# AVR-USB2SERIAL.net
KiCad netlist of a schematic drawn in EAGLE
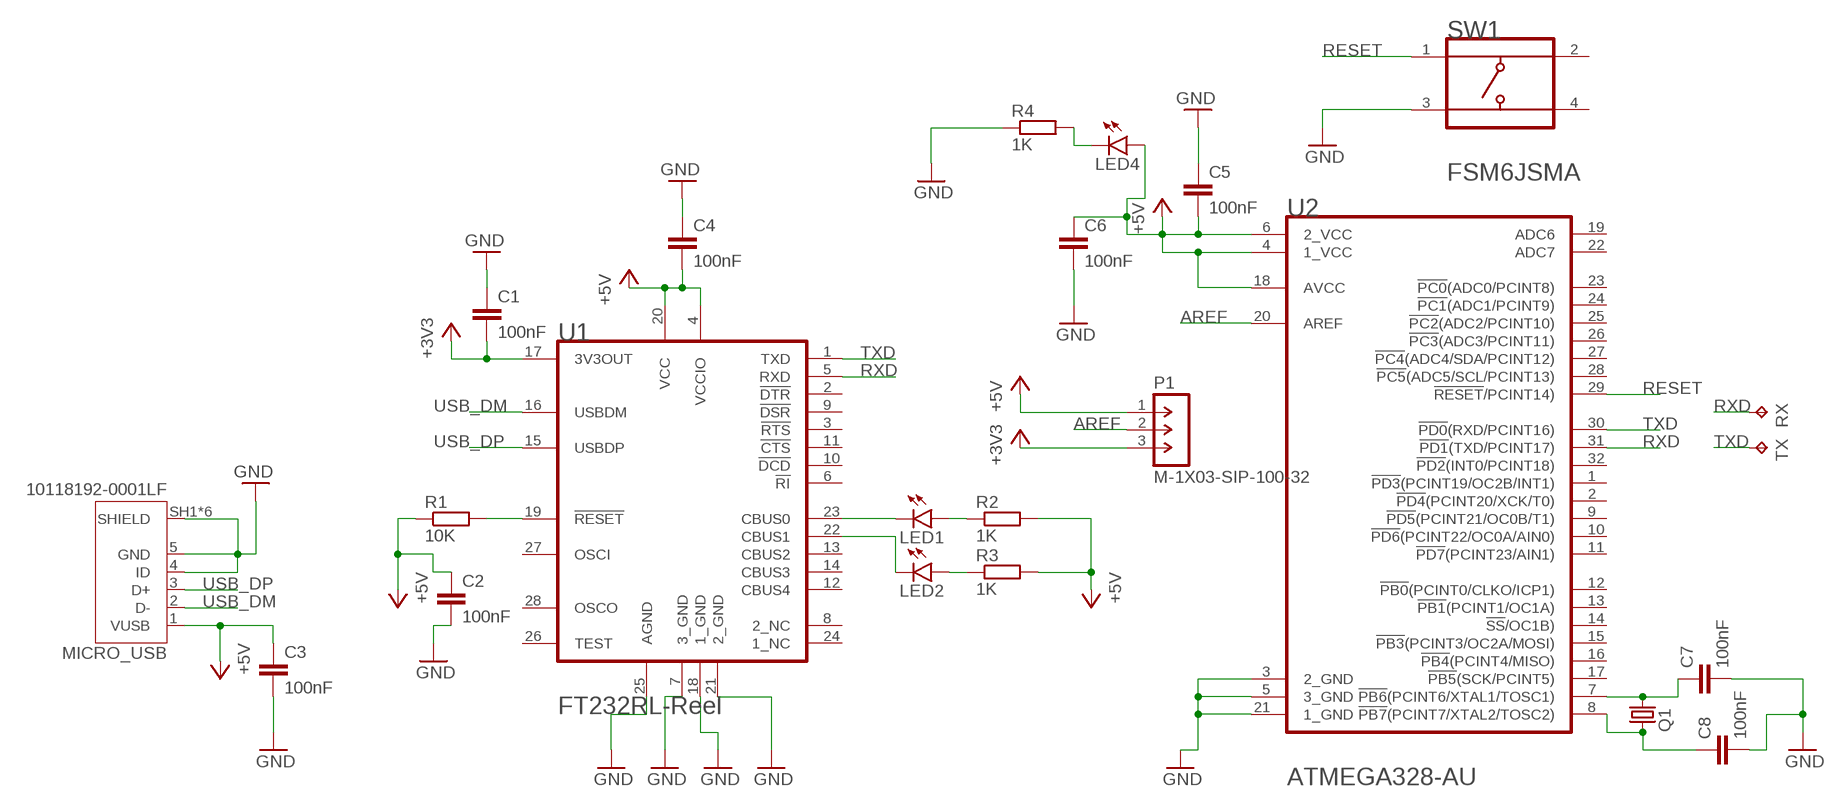
[diagram p0: schematic, sheet 1]

(export (version "E")
  (design (tool "Eeschema 10.0.6"))
  (components
    (comp (ref "C1")
      (value "100nF")
      (footprint "eagle-import:C0805")
      (libsource (lib "eagle-import") (part "C-EUC0805"))
    )
    (comp (ref "C2")
      (value "100nF")
      (footprint "eagle-import:C0805")
      (libsource (lib "eagle-import") (part "C-EUC0805"))
    )
    (comp (ref "C3")
      (value "100nF")
      (footprint "eagle-import:C0805")
      (libsource (lib "eagle-import") (part "C-EUC0805"))
    )
    (comp (ref "C4")
      (value "100nF")
      (footprint "eagle-import:C0805")
      (libsource (lib "eagle-import") (part "C-EUC0805"))
    )
    (comp (ref "C5")
      (value "100nF")
      (footprint "eagle-import:C0805")
      (libsource (lib "eagle-import") (part "C-EUC0805"))
    )
    (comp (ref "C6")
      (value "100nF")
      (footprint "eagle-import:C0805")
      (libsource (lib "eagle-import") (part "C-EUC0805"))
    )
    (comp (ref "C7")
      (value "100nF")
      (footprint "eagle-import:C0805")
      (libsource (lib "eagle-import") (part "C-EUC0805"))
    )
    (comp (ref "C8")
      (value "100nF")
      (footprint "eagle-import:C0805")
      (libsource (lib "eagle-import") (part "C-EUC0805"))
    )
    (comp (ref "LED1")
      (value "LEDCHIPLED_0805")
      (footprint "eagle-import:CHIPLED_0805")
      (libsource (lib "eagle-import") (part "LEDCHIPLED_0805"))
    )
    (comp (ref "LED2")
      (value "LEDCHIPLED_0805")
      (footprint "eagle-import:CHIPLED_0805")
      (libsource (lib "eagle-import") (part "LEDCHIPLED_0805"))
    )
    (comp (ref "LED4")
      (value "LEDCHIPLED_0805")
      (footprint "eagle-import:CHIPLED_0805")
      (libsource (lib "eagle-import") (part "LEDCHIPLED_0805"))
    )
    (comp (ref "MICRO_USB")
      (value "10118192-0001LF")
      (footprint "eagle-import:AMPHENOL_10118192-0001LF")
      (fields (field (name "MF") "Amphenol ICC"))
      (libsource (lib "eagle-import") (part "10118192-0001LF"))
    )
    (comp (ref "P1")
      (value "M-1X03-SIP-100-32")
      (footprint "eagle-import:SIP-100-03-32")
      (libsource (lib "eagle-import") (part "M-1X03-SIP-100-32"))
    )
    (comp (ref "Q1")
      (value "CRYSTALHC49UP")
      (footprint "eagle-import:HC49UP")
      (libsource (lib "eagle-import") (part "CRYSTALHC49UP"))
    )
    (comp (ref "R1")
      (value "10K")
      (footprint "eagle-import:R0805")
      (libsource (lib "eagle-import") (part "R-EU_R0805"))
    )
    (comp (ref "R2")
      (value "1K")
      (footprint "eagle-import:R0805")
      (libsource (lib "eagle-import") (part "R-EU_R0805"))
    )
    (comp (ref "R3")
      (value "1K")
      (footprint "eagle-import:R0805")
      (libsource (lib "eagle-import") (part "R-EU_R0805"))
    )
    (comp (ref "R4")
      (value "1K")
      (footprint "eagle-import:R0805")
      (libsource (lib "eagle-import") (part "R-EU_R0805"))
    )
    (comp (ref "RX")
      (value "TPB1,27")
      (footprint "eagle-import:B1,27")
      (libsource (lib "eagle-import") (part "TPB1,27"))
    )
    (comp (ref "SW1")
      (value "TE_CONNECTIVITY_ALCOSWITCH_FSM6JSMATE_CONNECTIVITY_ALCOSWITCH_FSM6JSMA_0_0")
      (footprint "eagle-import:TE_CONNECTIVITY_ALCOSWITCH_FSM6JSMA_0")
      (fields (field (name "MF") "TE Connectivity Alcoswitch") (field (name "MPN") "FSM6JSMA"))
      (libsource (lib "eagle-import") (part "TE_CONNECTIVITY_ALCOSWITCH_FSM6JSMATE_CONNECTIVITY_ALCOSWITCH_FSM6JSMA_0_0"))
    )
    (comp (ref "TX")
      (value "TPB1,27")
      (footprint "eagle-import:B1,27")
      (libsource (lib "eagle-import") (part "TPB1,27"))
    )
    (comp (ref "U1")
      (value "FTDI_FT232RL-REELFTDI_FT232RL-REEL_0_0")
      (footprint "eagle-import:FTDI_FT232RL-REEL_0")
      (fields (field (name "MF") "FTDI") (field (name "MPN") "FT232RL-Reel"))
      (libsource (lib "eagle-import") (part "FTDI_FT232RL-REELFTDI_FT232RL-REEL_0_0"))
    )
    (comp (ref "U2")
      (value "MICROCHIP_-_ATMEL_ATMEGA328-AUMICROCHIP_-_ATMEL_ATMEGA328-AU_0_0")
      (footprint "eagle-import:MICROCHIP_-_ATMEL_ATMEGA328-AU_0")
      (fields (field (name "MF") "Microchip / Atmel") (field (name "MPN") "ATMEGA328-AU"))
      (libsource (lib "eagle-import") (part "MICROCHIP_-_ATMEL_ATMEGA328-AUMICROCHIP_-_ATMEL_ATMEGA328-AU_0_0"))
    )
  )
  (nets
    (net (code "1") (name "+3V3") (class "Default")
      (node (ref "C1") (pin "2") (pinfunction "2_2") (pintype "passive"))
      (node (ref "P1") (pin "3") (pinfunction "3_3") (pintype "passive"))
      (node (ref "U1") (pin "17") (pinfunction "3V3OUT_17") (pintype "output"))
    )
    (net (code "2") (name "+5V") (class "Default")
      (node (ref "C2") (pin "1") (pinfunction "1_1") (pintype "passive"))
      (node (ref "C3") (pin "1") (pinfunction "1_1") (pintype "passive"))
      (node (ref "C4") (pin "2") (pinfunction "2_2") (pintype "passive"))
      (node (ref "C5") (pin "2") (pinfunction "2_2") (pintype "passive"))
      (node (ref "C6") (pin "1") (pinfunction "1_1") (pintype "passive"))
      (node (ref "LED4") (pin "A") (pinfunction "A_A") (pintype "passive"))
      (node (ref "MICRO_USB") (pin "1") (pinfunction "VUSB_1") (pintype "passive"))
      (node (ref "P1") (pin "1") (pinfunction "1_1") (pintype "passive"))
      (node (ref "R1") (pin "1") (pinfunction "1_1") (pintype "passive"))
      (node (ref "R2") (pin "2") (pinfunction "2_2") (pintype "passive"))
      (node (ref "R3") (pin "2") (pinfunction "2_2") (pintype "passive"))
      (node (ref "U1") (pin "20") (pinfunction "VCC_20") (pintype "power_in"))
      (node (ref "U1") (pin "4") (pinfunction "VCCIO_4") (pintype "power_in"))
      (node (ref "U2") (pin "18") (pinfunction "AVCC_18") (pintype "power_in"))
      (node (ref "U2") (pin "4") (pinfunction "1_VCC_4") (pintype "power_in"))
      (node (ref "U2") (pin "6") (pinfunction "2_VCC_6") (pintype "power_in"))
    )
    (net (code "3") (name "/AREF") (class "Default")
      (node (ref "P1") (pin "2") (pinfunction "2_2") (pintype "passive"))
      (node (ref "U2") (pin "20") (pinfunction "AREF_20") (pintype "passive"))
    )
    (net (code "4") (name "/RESET") (class "Default")
      (node (ref "SW1") (pin "1") (pinfunction "1_1") (pintype "passive"))
      (node (ref "U2") (pin "29") (pinfunction "~{RESET}/PCINT14)_29") (pintype "bidirectional"))
    )
    (net (code "5") (name "/RXD") (class "Default")
      (node (ref "RX") (pin "TP") (pinfunction "TP_TP") (pintype "input"))
      (node (ref "U1") (pin "5") (pinfunction "RXD_5") (pintype "input"))
      (node (ref "U2") (pin "31") (pinfunction "~{PD1}(TXD/PCINT17)_31") (pintype "bidirectional"))
    )
    (net (code "6") (name "/TXD") (class "Default")
      (node (ref "TX") (pin "TP") (pinfunction "TP_TP") (pintype "input"))
      (node (ref "U1") (pin "1") (pinfunction "TXD_1") (pintype "output"))
      (node (ref "U2") (pin "30") (pinfunction "~{PD0}(RXD/PCINT16)_30") (pintype "bidirectional"))
    )
    (net (code "7") (name "/USB_DM") (class "Default")
      (node (ref "MICRO_USB") (pin "2") (pinfunction "D-_2") (pintype "passive"))
      (node (ref "U1") (pin "16") (pinfunction "USBDM_16") (pintype "bidirectional"))
    )
    (net (code "8") (name "/USB_DP") (class "Default")
      (node (ref "MICRO_USB") (pin "3") (pinfunction "D+_3") (pintype "passive"))
      (node (ref "U1") (pin "15") (pinfunction "USBDP_15") (pintype "bidirectional"))
    )
    (net (code "9") (name "GND") (class "Default")
      (node (ref "C1") (pin "1") (pinfunction "1_1") (pintype "passive"))
      (node (ref "C2") (pin "2") (pinfunction "2_2") (pintype "passive"))
      (node (ref "C3") (pin "2") (pinfunction "2_2") (pintype "passive"))
      (node (ref "C4") (pin "1") (pinfunction "1_1") (pintype "passive"))
      (node (ref "C5") (pin "1") (pinfunction "1_1") (pintype "passive"))
      (node (ref "C6") (pin "2") (pinfunction "2_2") (pintype "passive"))
      (node (ref "C7") (pin "2") (pinfunction "2_2") (pintype "passive"))
      (node (ref "C8") (pin "2") (pinfunction "2_2") (pintype "passive"))
      (node (ref "MICRO_USB") (pin "4") (pinfunction "ID_4") (pintype "passive"))
      (node (ref "MICRO_USB") (pin "5") (pinfunction "GND_5") (pintype "passive"))
      (node (ref "MICRO_USB") (pin "SH1") (pinfunction "SHIELD_SH1") (pintype "passive"))
      (node (ref "MICRO_USB") (pin "SH2") (pinfunction "SHIELD_SH2") (pintype "passive"))
      (node (ref "MICRO_USB") (pin "SH3") (pinfunction "SHIELD_SH3") (pintype "passive"))
      (node (ref "MICRO_USB") (pin "SH4") (pinfunction "SHIELD_SH4") (pintype "passive"))
      (node (ref "MICRO_USB") (pin "SH5") (pinfunction "SHIELD_SH5") (pintype "passive"))
      (node (ref "MICRO_USB") (pin "SH6") (pinfunction "SHIELD_SH6") (pintype "passive"))
      (node (ref "R4") (pin "1") (pinfunction "1_1") (pintype "passive"))
      (node (ref "SW1") (pin "3") (pinfunction "3_3") (pintype "passive"))
      (node (ref "U1") (pin "18") (pinfunction "1_GND_18") (pintype "power_in"))
      (node (ref "U1") (pin "21") (pinfunction "2_GND_21") (pintype "power_in"))
      (node (ref "U1") (pin "25") (pinfunction "AGND_25") (pintype "power_in"))
      (node (ref "U1") (pin "7") (pinfunction "3_GND_7") (pintype "power_in"))
      (node (ref "U2") (pin "21") (pinfunction "1_GND_21") (pintype "power_in"))
      (node (ref "U2") (pin "3") (pinfunction "2_GND_3") (pintype "power_in"))
      (node (ref "U2") (pin "5") (pinfunction "3_GND_5") (pintype "power_in"))
    )
    (net (code "10") (name "Net-(LED1-PadA)") (class "Default")
      (node (ref "LED1") (pin "A") (pinfunction "A_A") (pintype "passive"))
      (node (ref "R2") (pin "1") (pinfunction "1_1") (pintype "passive"))
    )
    (net (code "11") (name "Net-(LED2-PadA)") (class "Default")
      (node (ref "LED2") (pin "A") (pinfunction "A_A") (pintype "passive"))
      (node (ref "R3") (pin "1") (pinfunction "1_1") (pintype "passive"))
    )
    (net (code "12") (name "Net-(LED4-PadC)") (class "Default")
      (node (ref "LED4") (pin "C") (pinfunction "C_C") (pintype "passive"))
      (node (ref "R4") (pin "2") (pinfunction "2_2") (pintype "passive"))
    )
    (net (code "13") (name "Net-(U1-CBUS0)") (class "Default")
      (node (ref "LED1") (pin "C") (pinfunction "C_C") (pintype "passive"))
      (node (ref "U1") (pin "23") (pinfunction "CBUS0_23") (pintype "bidirectional"))
    )
    (net (code "14") (name "Net-(U1-CBUS1)") (class "Default")
      (node (ref "LED2") (pin "C") (pinfunction "C_C") (pintype "passive"))
      (node (ref "U1") (pin "22") (pinfunction "CBUS1_22") (pintype "bidirectional"))
    )
    (net (code "15") (name "Net-(U1-~{RESET})") (class "Default")
      (node (ref "R1") (pin "2") (pinfunction "2_2") (pintype "passive"))
      (node (ref "U1") (pin "19") (pinfunction "~{RESET}_19") (pintype "input"))
    )
    (net (code "16") (name "Net-(U2-~{PB6}(PCINT6{slash}XTAL1{slash}TOSC1))") (class "Default")
      (node (ref "C7") (pin "1") (pinfunction "1_1") (pintype "passive"))
      (node (ref "Q1") (pin "2") (pinfunction "2_2") (pintype "passive"))
      (node (ref "U2") (pin "7") (pinfunction "~{PB6}(PCINT6/XTAL1/TOSC1)_7") (pintype "bidirectional"))
    )
    (net (code "17") (name "Net-(U2-~{PB7}(PCINT7{slash}XTAL2{slash}TOSC2))") (class "Default")
      (node (ref "C8") (pin "1") (pinfunction "1_1") (pintype "passive"))
      (node (ref "Q1") (pin "1") (pinfunction "1_1") (pintype "passive"))
      (node (ref "U2") (pin "8") (pinfunction "~{PB7}(PCINT7/XTAL2/TOSC2)_8") (pintype "bidirectional"))
    )
    (net (code "18") (name "unconnected-(SW1-Pad2)") (class "Default")
      (node (ref "SW1") (pin "2") (pinfunction "2_2") (pintype "passive"))
    )
    (net (code "19") (name "unconnected-(SW1-Pad4)") (class "Default")
      (node (ref "SW1") (pin "4") (pinfunction "4_4") (pintype "passive"))
    )
    (net (code "20") (name "unconnected-(U1-1_NC-Pad24)") (class "Default")
      (node (ref "U1") (pin "24") (pinfunction "1_NC_24") (pintype "passive"))
    )
    (net (code "21") (name "unconnected-(U1-2_NC-Pad8)") (class "Default")
      (node (ref "U1") (pin "8") (pinfunction "2_NC_8") (pintype "passive"))
    )
    (net (code "22") (name "unconnected-(U1-CBUS2-Pad13)") (class "Default")
      (node (ref "U1") (pin "13") (pinfunction "CBUS2_13") (pintype "bidirectional"))
    )
    (net (code "23") (name "unconnected-(U1-CBUS3-Pad14)") (class "Default")
      (node (ref "U1") (pin "14") (pinfunction "CBUS3_14") (pintype "bidirectional"))
    )
    (net (code "24") (name "unconnected-(U1-CBUS4-Pad12)") (class "Default")
      (node (ref "U1") (pin "12") (pinfunction "CBUS4_12") (pintype "bidirectional"))
    )
    (net (code "25") (name "unconnected-(U1-OSCI-Pad27)") (class "Default")
      (node (ref "U1") (pin "27") (pinfunction "OSCI_27") (pintype "input"))
    )
    (net (code "26") (name "unconnected-(U1-OSCO-Pad28)") (class "Default")
      (node (ref "U1") (pin "28") (pinfunction "OSCO_28") (pintype "output"))
    )
    (net (code "27") (name "unconnected-(U1-TEST-Pad26)") (class "Default")
      (node (ref "U1") (pin "26") (pinfunction "TEST_26") (pintype "input"))
    )
    (net (code "28") (name "unconnected-(U1-~{CTS}-Pad11)") (class "Default")
      (node (ref "U1") (pin "11") (pinfunction "~{CTS}_11") (pintype "input"))
    )
    (net (code "29") (name "unconnected-(U1-~{DCD}-Pad10)") (class "Default")
      (node (ref "U1") (pin "10") (pinfunction "~{DCD}_10") (pintype "input"))
    )
    (net (code "30") (name "unconnected-(U1-~{DSR}-Pad9)") (class "Default")
      (node (ref "U1") (pin "9") (pinfunction "~{DSR}_9") (pintype "input"))
    )
    (net (code "31") (name "unconnected-(U1-~{DTR}-Pad2)") (class "Default")
      (node (ref "U1") (pin "2") (pinfunction "~{DTR}_2") (pintype "output"))
    )
    (net (code "32") (name "unconnected-(U1-~{RI}-Pad6)") (class "Default")
      (node (ref "U1") (pin "6") (pinfunction "~{RI}_6") (pintype "input"))
    )
    (net (code "33") (name "unconnected-(U1-~{RTS}-Pad3)") (class "Default")
      (node (ref "U1") (pin "3") (pinfunction "~{RTS}_3") (pintype "output"))
    )
    (net (code "34") (name "unconnected-(U2-ADC6-Pad19)") (class "Default")
      (node (ref "U2") (pin "19") (pinfunction "ADC6_19") (pintype "input"))
    )
    (net (code "35") (name "unconnected-(U2-ADC7-Pad22)") (class "Default")
      (node (ref "U2") (pin "22") (pinfunction "ADC7_22") (pintype "input"))
    )
    (net (code "36") (name "unconnected-(U2-~{PB0}(PCINT0{slash}CLKO{slash}ICP1)-Pad12)") (class "Default")
      (node (ref "U2") (pin "12") (pinfunction "~{PB0}(PCINT0/CLKO/ICP1)_12") (pintype "bidirectional"))
    )
    (net (code "37") (name "unconnected-(U2-~{PB1}(PCINT1{slash}OC1A)-Pad13)") (class "Default")
      (node (ref "U2") (pin "13") (pinfunction "~{PB1}(PCINT1/OC1A)_13") (pintype "bidirectional"))
    )
    (net (code "38") (name "unconnected-(U2-~{PB3}(PCINT3{slash}OC2A{slash}MOSI)-Pad15)") (class "Default")
      (node (ref "U2") (pin "15") (pinfunction "~{PB3}(PCINT3/OC2A/MOSI)_15") (pintype "bidirectional"))
    )
    (net (code "39") (name "unconnected-(U2-~{PB4}(PCINT4{slash}MISO)-Pad16)") (class "Default")
      (node (ref "U2") (pin "16") (pinfunction "~{PB4}(PCINT4/MISO)_16") (pintype "bidirectional"))
    )
    (net (code "40") (name "unconnected-(U2-~{PB5}(SCK{slash}PCINT5)-Pad17)") (class "Default")
      (node (ref "U2") (pin "17") (pinfunction "~{PB5}(SCK/PCINT5)_17") (pintype "bidirectional"))
    )
    (net (code "41") (name "unconnected-(U2-~{PC0}(ADC0{slash}PCINT8)-Pad23)") (class "Default")
      (node (ref "U2") (pin "23") (pinfunction "~{PC0}(ADC0/PCINT8)_23") (pintype "bidirectional"))
    )
    (net (code "42") (name "unconnected-(U2-~{PC1}(ADC1{slash}PCINT9)-Pad24)") (class "Default")
      (node (ref "U2") (pin "24") (pinfunction "~{PC1}(ADC1/PCINT9)_24") (pintype "bidirectional"))
    )
    (net (code "43") (name "unconnected-(U2-~{PC2}(ADC2{slash}PCINT10)-Pad25)") (class "Default")
      (node (ref "U2") (pin "25") (pinfunction "~{PC2}(ADC2/PCINT10)_25") (pintype "bidirectional"))
    )
    (net (code "44") (name "unconnected-(U2-~{PC3}(ADC3{slash}PCINT11)-Pad26)") (class "Default")
      (node (ref "U2") (pin "26") (pinfunction "~{PC3}(ADC3/PCINT11)_26") (pintype "bidirectional"))
    )
    (net (code "45") (name "unconnected-(U2-~{PC4}(ADC4{slash}SDA{slash}PCINT12)-Pad27)") (class "Default")
      (node (ref "U2") (pin "27") (pinfunction "~{PC4}(ADC4/SDA/PCINT12)_27") (pintype "bidirectional"))
    )
    (net (code "46") (name "unconnected-(U2-~{PC5}(ADC5{slash}SCL{slash}PCINT13)-Pad28)") (class "Default")
      (node (ref "U2") (pin "28") (pinfunction "~{PC5}(ADC5/SCL/PCINT13)_28") (pintype "bidirectional"))
    )
    (net (code "47") (name "unconnected-(U2-~{PD2}(INT0{slash}PCINT18)-Pad32)") (class "Default")
      (node (ref "U2") (pin "32") (pinfunction "~{PD2}(INT0/PCINT18)_32") (pintype "bidirectional"))
    )
    (net (code "48") (name "unconnected-(U2-~{PD3}(PCINT19{slash}OC2B{slash}INT1)-Pad1)") (class "Default")
      (node (ref "U2") (pin "1") (pinfunction "~{PD3}(PCINT19/OC2B/INT1)_1") (pintype "bidirectional"))
    )
    (net (code "49") (name "unconnected-(U2-~{PD4}(PCINT20{slash}XCK{slash}T0)-Pad2)") (class "Default")
      (node (ref "U2") (pin "2") (pinfunction "~{PD4}(PCINT20/XCK/T0)_2") (pintype "bidirectional"))
    )
    (net (code "50") (name "unconnected-(U2-~{PD5}(PCINT21{slash}OC0B{slash}T1)-Pad9)") (class "Default")
      (node (ref "U2") (pin "9") (pinfunction "~{PD5}(PCINT21/OC0B/T1)_9") (pintype "bidirectional"))
    )
    (net (code "51") (name "unconnected-(U2-~{PD6}(PCINT22{slash}OC0A{slash}AIN0)-Pad10)") (class "Default")
      (node (ref "U2") (pin "10") (pinfunction "~{PD6}(PCINT22/OC0A/AIN0)_10") (pintype "bidirectional"))
    )
    (net (code "52") (name "unconnected-(U2-~{PD7}(PCINT23{slash}AIN1)-Pad11)") (class "Default")
      (node (ref "U2") (pin "11") (pinfunction "~{PD7}(PCINT23/AIN1)_11") (pintype "bidirectional"))
    )
    (net (code "53") (name "unconnected-(U2-~{SS}{slash}OC1B)-Pad14)") (class "Default")
      (node (ref "U2") (pin "14") (pinfunction "~{SS}/OC1B)_14") (pintype "bidirectional"))
    )
  )
)
